# violin.net
KiCad netlist of a schematic drawn in EAGLE
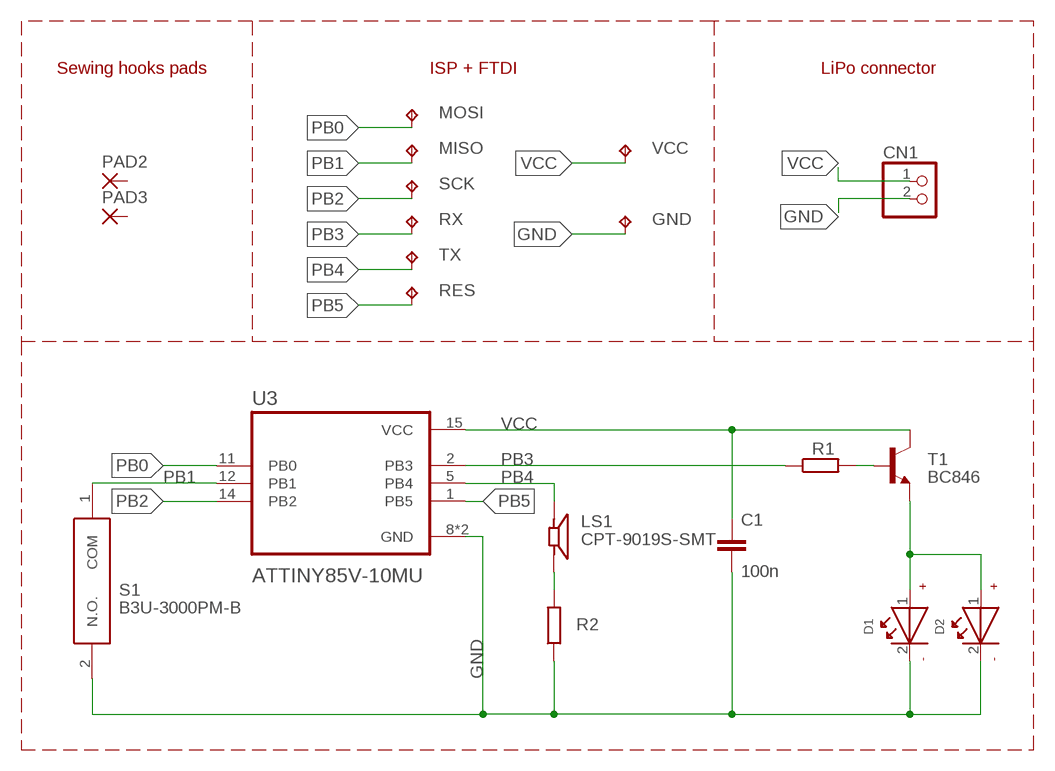
[diagram p0: schematic, sheet 1]

(export (version "E")
  (design (tool "Eeschema 10.0.6"))
  (components
    (comp (ref "C1")
      (value "100n")
      (footprint "eagle-import:C0603")
      (libsource (lib "eagle-import") (part "C-EUC0603"))
    )
    (comp (ref "CN1")
      (value "JST_2PIN")
      (footprint "eagle-import:JSTPH2")
      (libsource (lib "eagle-import") (part "JST_2PIN"))
    )
    (comp (ref "D1")
      (value "WL-SMSW155124YS73200-Y")
      (footprint "eagle-import:WL-SMSW_1204")
      (fields (field (name "MF") "Wurth Electronics") (field (name "MP") "155124YS73200"))
      (libsource (lib "eagle-import") (part "WL-SMSW155124YS73200-Y"))
    )
    (comp (ref "D2")
      (value "WL-SMSW155124YS73200-Y")
      (footprint "eagle-import:WL-SMSW_1204")
      (fields (field (name "MF") "Wurth Electronics") (field (name "MP") "155124YS73200"))
      (libsource (lib "eagle-import") (part "WL-SMSW155124YS73200-Y"))
    )
    (comp (ref "GND")
      (value "TPTP11SQ")
      (footprint "eagle-import:TP11SQ")
      (libsource (lib "eagle-import") (part "TPTP11SQ"))
    )
    (comp (ref "LS1")
      (value "CPT-9019S-SMT")
      (footprint "eagle-import:CUI_CPT-9019S-SMT")
      (fields (field (name "MF") "CUI Devices") (field (name "MP") "CPT-9019S-SMT-TR"))
      (libsource (lib "eagle-import") (part "CPT-9019S-SMT"))
    )
    (comp (ref "MISO")
      (value "TPTP11SQ")
      (footprint "eagle-import:TP11SQ")
      (libsource (lib "eagle-import") (part "TPTP11SQ"))
    )
    (comp (ref "MOSI")
      (value "TPTP11SQ")
      (footprint "eagle-import:TP11SQ")
      (libsource (lib "eagle-import") (part "TPTP11SQ"))
    )
    (comp (ref "PAD2")
      (value "SMD5")
      (footprint "eagle-import:SMD2,54-5,08")
      (libsource (lib "eagle-import") (part "SMD5"))
    )
    (comp (ref "PAD3")
      (value "SMD2")
      (footprint "eagle-import:SMD1,27-2,54")
      (libsource (lib "eagle-import") (part "SMD2"))
    )
    (comp (ref "R1")
      (value "R-EU_R0603")
      (footprint "eagle-import:R0603")
      (libsource (lib "eagle-import") (part "R-EU_R0603"))
    )
    (comp (ref "R2")
      (value "R-EU_R0603")
      (footprint "eagle-import:R0603")
      (libsource (lib "eagle-import") (part "R-EU_R0603"))
    )
    (comp (ref "RES")
      (value "TPTP11SQ")
      (footprint "eagle-import:TP11SQ")
      (libsource (lib "eagle-import") (part "TPTP11SQ"))
    )
    (comp (ref "RX")
      (value "TPTP11SQ")
      (footprint "eagle-import:TP11SQ")
      (libsource (lib "eagle-import") (part "TPTP11SQ"))
    )
    (comp (ref "S1")
      (value "B3U-3000PM-B")
      (footprint "eagle-import:B3U3000PMB")
      (fields (field (name "MOUSER_PART_NUMBER") "653-B3U-3000PM-B"))
      (libsource (lib "eagle-import") (part "B3U-3000PM-B"))
    )
    (comp (ref "SCK")
      (value "TPTP11SQ")
      (footprint "eagle-import:TP11SQ")
      (libsource (lib "eagle-import") (part "TPTP11SQ"))
    )
    (comp (ref "T1")
      (value "BC846")
      (footprint "eagle-import:SOT23")
      (libsource (lib "eagle-import") (part "BC846"))
    )
    (comp (ref "TX")
      (value "TPTP11SQ")
      (footprint "eagle-import:TP11SQ")
      (libsource (lib "eagle-import") (part "TPTP11SQ"))
    )
    (comp (ref "U3")
      (value "ATTINY85V-10MU")
      (footprint "eagle-import:QFN50P400X400X80-21N")
      (fields (field (name "MF") "Microchip"))
      (libsource (lib "eagle-import") (part "ATTINY85V-10MU"))
    )
    (comp (ref "VCC")
      (value "TPTP11SQ")
      (footprint "eagle-import:TP11SQ")
      (libsource (lib "eagle-import") (part "TPTP11SQ"))
    )
  )
  (nets
    (net (code "1") (name "GND") (class "Default")
      (node (ref "C1") (pin "2") (pinfunction "2_2") (pintype "passive"))
      (node (ref "CN1") (pin "2") (pinfunction "2_2") (pintype "passive"))
      (node (ref "D1") (pin "2") (pinfunction "-_2") (pintype "bidirectional"))
      (node (ref "D2") (pin "2") (pinfunction "-_2") (pintype "bidirectional"))
      (node (ref "GND") (pin "TP") (pinfunction "TP_TP") (pintype "input"))
      (node (ref "R2") (pin "1") (pinfunction "1_1") (pintype "passive"))
      (node (ref "S1") (pin "2") (pinfunction "N.O._2") (pintype "bidirectional"))
      (node (ref "U3") (pin "21") (pinfunction "GND_21") (pintype "power_in"))
      (node (ref "U3") (pin "8") (pinfunction "GND_8") (pintype "power_in"))
    )
    (net (code "2") (name "Net-(D1-+)") (class "Default")
      (node (ref "D1") (pin "1") (pinfunction "+_1") (pintype "bidirectional"))
      (node (ref "D2") (pin "1") (pinfunction "+_1") (pintype "bidirectional"))
      (node (ref "T1") (pin "2") (pinfunction "E_2") (pintype "passive"))
    )
    (net (code "3") (name "Net-(LS1-Pad2)") (class "Default")
      (node (ref "LS1") (pin "2") (pinfunction "2_2") (pintype "passive"))
      (node (ref "R2") (pin "2") (pinfunction "2_2") (pintype "passive"))
    )
    (net (code "4") (name "Net-(T1-B)") (class "Default")
      (node (ref "R1") (pin "2") (pinfunction "2_2") (pintype "passive"))
      (node (ref "T1") (pin "1") (pinfunction "B_1") (pintype "passive"))
    )
    (net (code "5") (name "PB0") (class "Default")
      (node (ref "MOSI") (pin "TP") (pinfunction "TP_TP") (pintype "input"))
      (node (ref "U3") (pin "11") (pinfunction "PB0_11") (pintype "bidirectional"))
    )
    (net (code "6") (name "PB1") (class "Default")
      (node (ref "MISO") (pin "TP") (pinfunction "TP_TP") (pintype "input"))
      (node (ref "S1") (pin "1") (pinfunction "COM_1") (pintype "bidirectional"))
      (node (ref "U3") (pin "12") (pinfunction "PB1_12") (pintype "bidirectional"))
    )
    (net (code "7") (name "PB2") (class "Default")
      (node (ref "SCK") (pin "TP") (pinfunction "TP_TP") (pintype "input"))
      (node (ref "U3") (pin "14") (pinfunction "PB2_14") (pintype "bidirectional"))
    )
    (net (code "8") (name "PB3") (class "Default")
      (node (ref "R1") (pin "1") (pinfunction "1_1") (pintype "passive"))
      (node (ref "RX") (pin "TP") (pinfunction "TP_TP") (pintype "input"))
      (node (ref "U3") (pin "2") (pinfunction "PB3_2") (pintype "bidirectional"))
    )
    (net (code "9") (name "PB4") (class "Default")
      (node (ref "LS1") (pin "1") (pinfunction "1_1") (pintype "passive"))
      (node (ref "TX") (pin "TP") (pinfunction "TP_TP") (pintype "input"))
      (node (ref "U3") (pin "5") (pinfunction "PB4_5") (pintype "bidirectional"))
    )
    (net (code "10") (name "PB5") (class "Default")
      (node (ref "RES") (pin "TP") (pinfunction "TP_TP") (pintype "input"))
      (node (ref "U3") (pin "1") (pinfunction "PB5_1") (pintype "bidirectional"))
    )
    (net (code "11") (name "VCC") (class "Default")
      (node (ref "C1") (pin "1") (pinfunction "1_1") (pintype "passive"))
      (node (ref "CN1") (pin "1") (pinfunction "1_1") (pintype "passive"))
      (node (ref "T1") (pin "3") (pinfunction "C_3") (pintype "passive"))
      (node (ref "U3") (pin "15") (pinfunction "VCC_15") (pintype "power_in"))
      (node (ref "VCC") (pin "TP") (pinfunction "TP_TP") (pintype "input"))
    )
    (net (code "12") (name "unconnected-(PAD2-P-Pad1)") (class "Default")
      (node (ref "PAD2") (pin "1") (pinfunction "P_1") (pintype "passive"))
    )
    (net (code "13") (name "unconnected-(PAD3-P-Pad1)") (class "Default")
      (node (ref "PAD3") (pin "1") (pinfunction "P_1") (pintype "passive"))
    )
  )
)
